# PIC18F2550-USB-HID-LC-Meter.net
KiCad netlist of a schematic drawn in EAGLE
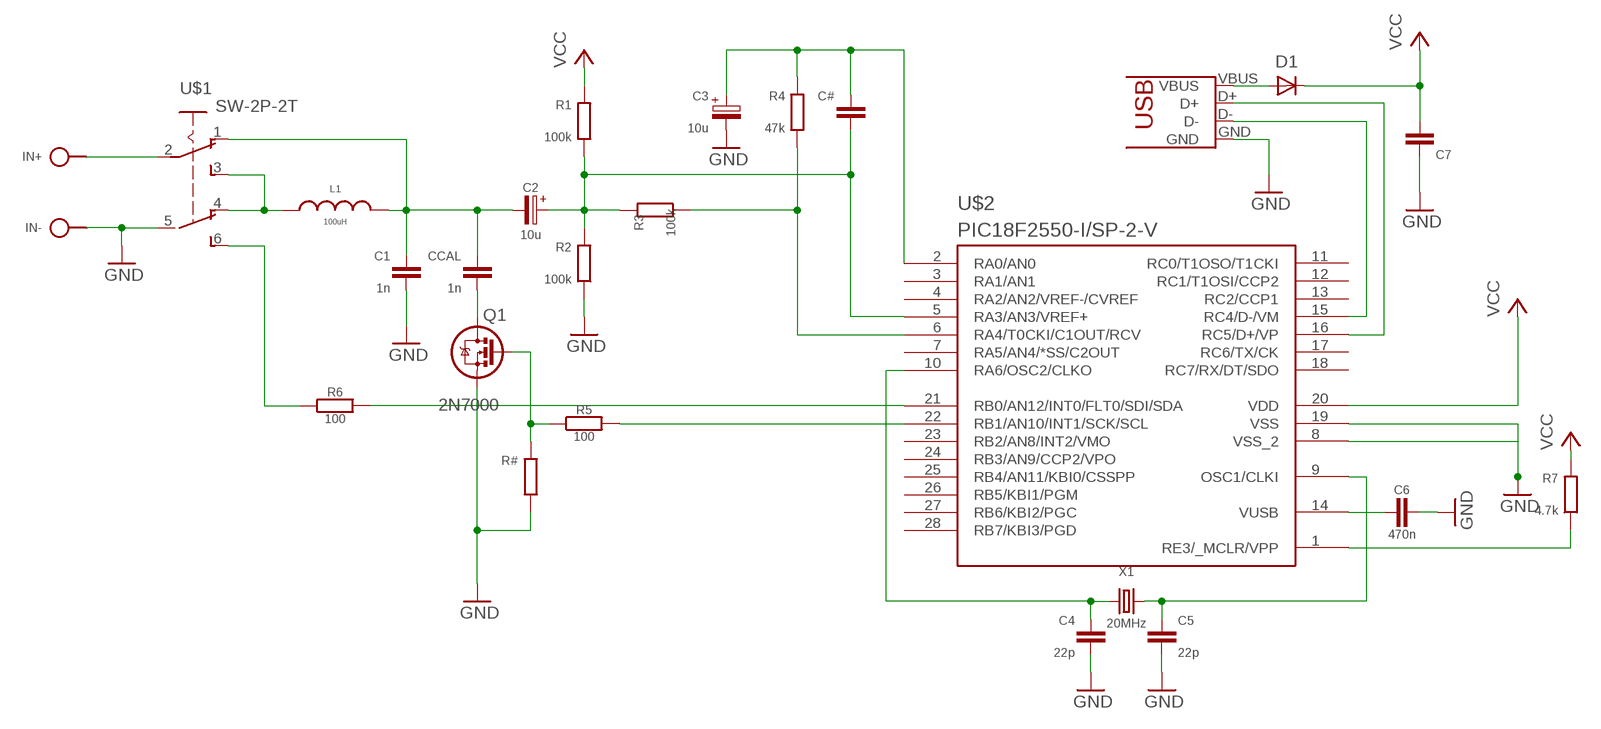
[diagram p0: schematic, sheet 1]

(export (version "E")
  (design (tool "Eeschema 10.0.6"))
  (components
    (comp (ref "C#")
      (value "C050-020X036")
      (footprint "eagle-import:C050-020X036")
      (libsource (lib "eagle-import") (part "C050-020X036"))
    )
    (comp (ref "C1")
      (value "1n")
      (footprint "eagle-import:C050-020X036")
      (libsource (lib "eagle-import") (part "C050-020X036"))
    )
    (comp (ref "C2")
      (value "10u")
      (footprint "eagle-import:E2.5-4_V")
      (libsource (lib "eagle-import") (part "CPOLE2,5-4/V"))
    )
    (comp (ref "C3")
      (value "10u")
      (footprint "eagle-import:E2,5-4")
      (libsource (lib "eagle-import") (part "CPOLE2,5-4"))
    )
    (comp (ref "C4")
      (value "22p")
      (footprint "eagle-import:C025-015X024_V")
      (libsource (lib "eagle-import") (part "C025-015X024"))
    )
    (comp (ref "C5")
      (value "22p")
      (footprint "eagle-import:C025-015X024_V")
      (libsource (lib "eagle-import") (part "C025-015X024"))
    )
    (comp (ref "C6")
      (value "470n")
      (footprint "eagle-import:C050-020X036")
      (libsource (lib "eagle-import") (part "C050-020X036"))
    )
    (comp (ref "C7")
      (value "C050-020X036")
      (footprint "eagle-import:C050-020X036")
      (libsource (lib "eagle-import") (part "C050-020X036"))
    )
    (comp (ref "CCAL")
      (value "1n")
      (footprint "eagle-import:C050-020X036")
      (libsource (lib "eagle-import") (part "C050-020X036"))
    )
    (comp (ref "D1")
      (value "1N414834-5")
      (footprint "eagle-import:DO34-5")
      (libsource (lib "eagle-import") (part "1N414834-5"))
    )
    (comp (ref "IN+")
      (value "SPAD")
      (footprint "eagle-import:SPAD")
      (libsource (lib "eagle-import") (part "SPAD"))
    )
    (comp (ref "IN-")
      (value "SPAD")
      (footprint "eagle-import:SPAD")
      (libsource (lib "eagle-import") (part "SPAD"))
    )
    (comp (ref "J1")
      (value "USB-PRINT")
      (footprint "eagle-import:USB-B-PRINT")
      (libsource (lib "eagle-import") (part "USB-PRINT"))
    )
    (comp (ref "L1")
      (value "100uH")
      (footprint "eagle-import:L-04_7-M")
      (libsource (lib "eagle-import") (part "L04/7-M"))
    )
    (comp (ref "Q1")
      (value "2N7000")
      (footprint "eagle-import:TO92")
      (libsource (lib "eagle-import") (part "2N7000"))
    )
    (comp (ref "R#")
      (value "R0202/7")
      (footprint "eagle-import:0202_7")
      (libsource (lib "eagle-import") (part "R0202/7"))
    )
    (comp (ref "R1")
      (value "100k")
      (footprint "eagle-import:0202_7")
      (libsource (lib "eagle-import") (part "R0202/7"))
    )
    (comp (ref "R2")
      (value "100k")
      (footprint "eagle-import:0202_7")
      (libsource (lib "eagle-import") (part "R0202/7"))
    )
    (comp (ref "R3")
      (value "100k")
      (footprint "eagle-import:0202_7")
      (libsource (lib "eagle-import") (part "R0202/7"))
    )
    (comp (ref "R4")
      (value "47k")
      (footprint "eagle-import:0202_7")
      (libsource (lib "eagle-import") (part "R0202/7"))
    )
    (comp (ref "R5")
      (value "100")
      (footprint "eagle-import:0202_7")
      (libsource (lib "eagle-import") (part "R0202/7"))
    )
    (comp (ref "R6")
      (value "100")
      (footprint "eagle-import:0202_7")
      (libsource (lib "eagle-import") (part "R0202/7"))
    )
    (comp (ref "R7")
      (value "4.7k")
      (footprint "eagle-import:0202_7")
      (libsource (lib "eagle-import") (part "R0202/7"))
    )
    (comp (ref "U$1")
      (value "SW-2P-2T")
      (footprint "eagle-import:SLSW-2P2T")
      (libsource (lib "eagle-import") (part "SW-2P-2T"))
    )
    (comp (ref "U$2")
      (value "PIC18F2550-I/SP-2-V")
      (footprint "eagle-import:DIL28-3_V")
      (libsource (lib "eagle-import") (part "PIC18F2550-I/SP-2-V"))
    )
    (comp (ref "X1")
      (value "20MHz")
      (footprint "eagle-import:HC49")
      (libsource (lib "eagle-import") (part "CRYSTALHC49"))
    )
  )
  (nets
    (net (code "1") (name "GND") (class "Default")
      (node (ref "C1") (pin "2") (pinfunction "2_2") (pintype "passive"))
      (node (ref "C3") (pin "-") (pinfunction "-_-") (pintype "passive"))
      (node (ref "C4") (pin "2") (pinfunction "2_2") (pintype "passive"))
      (node (ref "C5") (pin "2") (pinfunction "2_2") (pintype "passive"))
      (node (ref "C6") (pin "2") (pinfunction "2_2") (pintype "passive"))
      (node (ref "C7") (pin "1") (pinfunction "1_1") (pintype "passive"))
      (node (ref "IN-") (pin "1") (pinfunction "P$1_1") (pintype "bidirectional"))
      (node (ref "J1") (pin "GND") (pinfunction "GND_GND") (pintype "bidirectional"))
      (node (ref "Q1") (pin "1") (pinfunction "S_1") (pintype "passive"))
      (node (ref "R#") (pin "1") (pinfunction "1_1") (pintype "passive"))
      (node (ref "R2") (pin "1") (pinfunction "1_1") (pintype "passive"))
      (node (ref "U$1") (pin "5") (pinfunction "P1_5") (pintype "passive"))
      (node (ref "U$2") (pin "19") (pinfunction "VSS_19") (pintype "passive"))
      (node (ref "U$2") (pin "8") (pinfunction "VSS_2_8") (pintype "passive"))
    )
    (net (code "2") (name "Net-(D1-PadA)") (class "Default")
      (node (ref "D1") (pin "A") (pinfunction "A_A") (pintype "passive"))
      (node (ref "J1") (pin "VBUS") (pinfunction "VBUS_VBUS") (pintype "bidirectional"))
    )
    (net (code "3") (name "Net-(IN+-P$1)") (class "Default")
      (node (ref "IN+") (pin "1") (pinfunction "P$1_1") (pintype "bidirectional"))
      (node (ref "U$1") (pin "2") (pinfunction "P_2") (pintype "passive"))
    )
    (net (code "4") (name "Net-(Q1-D)") (class "Default")
      (node (ref "CCAL") (pin "2") (pinfunction "2_2") (pintype "passive"))
      (node (ref "Q1") (pin "3") (pinfunction "D_3") (pintype "passive"))
    )
    (net (code "5") (name "Net-(Q1-G)") (class "Default")
      (node (ref "Q1") (pin "2") (pinfunction "G_2") (pintype "passive"))
      (node (ref "R#") (pin "2") (pinfunction "2_2") (pintype "passive"))
      (node (ref "R5") (pin "1") (pinfunction "1_1") (pintype "passive"))
    )
    (net (code "6") (name "Net-(U$1-O)") (class "Default")
      (node (ref "C1") (pin "1") (pinfunction "1_1") (pintype "passive"))
      (node (ref "C2") (pin "-") (pinfunction "-_-") (pintype "passive"))
      (node (ref "CCAL") (pin "1") (pinfunction "1_1") (pintype "passive"))
      (node (ref "L1") (pin "2") (pinfunction "2_2") (pintype "passive"))
      (node (ref "U$1") (pin "1") (pinfunction "O_1") (pintype "passive"))
    )
    (net (code "7") (name "Net-(U$1-O1)") (class "Default")
      (node (ref "L1") (pin "1") (pinfunction "1_1") (pintype "passive"))
      (node (ref "U$1") (pin "3") (pinfunction "S_3") (pintype "passive"))
      (node (ref "U$1") (pin "4") (pinfunction "O1_4") (pintype "passive"))
    )
    (net (code "8") (name "Net-(U$1-S1)") (class "Default")
      (node (ref "R6") (pin "1") (pinfunction "1_1") (pintype "passive"))
      (node (ref "U$1") (pin "6") (pinfunction "S1_6") (pintype "passive"))
    )
    (net (code "9") (name "Net-(U$2-OSC1{slash}CLKI)") (class "Default")
      (node (ref "C5") (pin "1") (pinfunction "1_1") (pintype "passive"))
      (node (ref "U$2") (pin "9") (pinfunction "OSC1/CLKI_9") (pintype "passive"))
      (node (ref "X1") (pin "2") (pinfunction "2_2") (pintype "passive"))
    )
    (net (code "10") (name "Net-(U$2-RA0{slash}AN0)") (class "Default")
      (node (ref "C#") (pin "1") (pinfunction "1_1") (pintype "passive"))
      (node (ref "C3") (pin "+") (pinfunction "+_+") (pintype "passive"))
      (node (ref "R4") (pin "2") (pinfunction "2_2") (pintype "passive"))
      (node (ref "U$2") (pin "2") (pinfunction "RA0/AN0_2") (pintype "passive"))
    )
    (net (code "11") (name "Net-(U$2-RA3{slash}AN3{slash}VREF+)") (class "Default")
      (node (ref "C#") (pin "2") (pinfunction "2_2") (pintype "passive"))
      (node (ref "C2") (pin "+") (pinfunction "+_+") (pintype "passive"))
      (node (ref "R1") (pin "1") (pinfunction "1_1") (pintype "passive"))
      (node (ref "R2") (pin "2") (pinfunction "2_2") (pintype "passive"))
      (node (ref "R3") (pin "2") (pinfunction "2_2") (pintype "passive"))
      (node (ref "U$2") (pin "5") (pinfunction "RA3/AN3/VREF+_5") (pintype "passive"))
    )
    (net (code "12") (name "Net-(U$2-RA4{slash}T0CKI{slash}C1OUT{slash}RCV)") (class "Default")
      (node (ref "R3") (pin "1") (pinfunction "1_1") (pintype "passive"))
      (node (ref "R4") (pin "1") (pinfunction "1_1") (pintype "passive"))
      (node (ref "U$2") (pin "6") (pinfunction "RA4/T0CKI/C1OUT/RCV_6") (pintype "passive"))
    )
    (net (code "13") (name "Net-(U$2-RA6{slash}OSC2{slash}CLKO)") (class "Default")
      (node (ref "C4") (pin "1") (pinfunction "1_1") (pintype "passive"))
      (node (ref "U$2") (pin "10") (pinfunction "RA6/OSC2/CLKO_10") (pintype "passive"))
      (node (ref "X1") (pin "1") (pinfunction "1_1") (pintype "passive"))
    )
    (net (code "14") (name "Net-(U$2-RB0{slash}AN12{slash}INT0{slash}FLT0{slash}SDI{slash}SDA)") (class "Default")
      (node (ref "R6") (pin "2") (pinfunction "2_2") (pintype "passive"))
      (node (ref "U$2") (pin "21") (pinfunction "RB0/AN12/INT0/FLT0/SDI/SDA_21") (pintype "passive"))
    )
    (net (code "15") (name "Net-(U$2-RB1{slash}AN10{slash}INT1{slash}SCK{slash}SCL)") (class "Default")
      (node (ref "R5") (pin "2") (pinfunction "2_2") (pintype "passive"))
      (node (ref "U$2") (pin "22") (pinfunction "RB1/AN10/INT1/SCK/SCL_22") (pintype "passive"))
    )
    (net (code "16") (name "Net-(U$2-RC4{slash}D-{slash}VM)") (class "Default")
      (node (ref "J1") (pin "D-") (pinfunction "D-_D-") (pintype "bidirectional"))
      (node (ref "U$2") (pin "15") (pinfunction "RC4/D-/VM_15") (pintype "passive"))
    )
    (net (code "17") (name "Net-(U$2-RC5{slash}D+{slash}VP)") (class "Default")
      (node (ref "J1") (pin "D+") (pinfunction "D+_D+") (pintype "bidirectional"))
      (node (ref "U$2") (pin "16") (pinfunction "RC5/D+/VP_16") (pintype "passive"))
    )
    (net (code "18") (name "Net-(U$2-RE3{slash}_MCLR{slash}VPP)") (class "Default")
      (node (ref "R7") (pin "1") (pinfunction "1_1") (pintype "passive"))
      (node (ref "U$2") (pin "1") (pinfunction "RE3/_MCLR/VPP_1") (pintype "passive"))
    )
    (net (code "19") (name "Net-(U$2-VUSB)") (class "Default")
      (node (ref "C6") (pin "1") (pinfunction "1_1") (pintype "passive"))
      (node (ref "U$2") (pin "14") (pinfunction "VUSB_14") (pintype "passive"))
    )
    (net (code "20") (name "VCC") (class "Default")
      (node (ref "C7") (pin "2") (pinfunction "2_2") (pintype "passive"))
      (node (ref "D1") (pin "C") (pinfunction "C_C") (pintype "passive"))
      (node (ref "R1") (pin "2") (pinfunction "2_2") (pintype "passive"))
      (node (ref "R7") (pin "2") (pinfunction "2_2") (pintype "passive"))
      (node (ref "U$2") (pin "20") (pinfunction "VDD_20") (pintype "passive"))
    )
    (net (code "21") (name "unconnected-(U$2-RA1{slash}AN1-Pad3)") (class "Default")
      (node (ref "U$2") (pin "3") (pinfunction "RA1/AN1_3") (pintype "passive"))
    )
    (net (code "22") (name "unconnected-(U$2-RA2{slash}AN2{slash}VREF-{slash}CVREF-Pad4)") (class "Default")
      (node (ref "U$2") (pin "4") (pinfunction "RA2/AN2/VREF-/CVREF_4") (pintype "passive"))
    )
    (net (code "23") (name "unconnected-(U$2-RA5{slash}AN4{slash}*SS{slash}C2OUT-Pad7)") (class "Default")
      (node (ref "U$2") (pin "7") (pinfunction "RA5/AN4/*SS/C2OUT_7") (pintype "passive"))
    )
    (net (code "24") (name "unconnected-(U$2-RB2{slash}AN8{slash}INT2{slash}VMO-Pad23)") (class "Default")
      (node (ref "U$2") (pin "23") (pinfunction "RB2/AN8/INT2/VMO_23") (pintype "passive"))
    )
    (net (code "25") (name "unconnected-(U$2-RB3{slash}AN9{slash}CCP2{slash}VPO-Pad24)") (class "Default")
      (node (ref "U$2") (pin "24") (pinfunction "RB3/AN9/CCP2/VPO_24") (pintype "passive"))
    )
    (net (code "26") (name "unconnected-(U$2-RB4{slash}AN11{slash}KBI0{slash}CSSPP-Pad25)") (class "Default")
      (node (ref "U$2") (pin "25") (pinfunction "RB4/AN11/KBI0/CSSPP_25") (pintype "passive"))
    )
    (net (code "27") (name "unconnected-(U$2-RB5{slash}KBI1{slash}PGM-Pad26)") (class "Default")
      (node (ref "U$2") (pin "26") (pinfunction "RB5/KBI1/PGM_26") (pintype "passive"))
    )
    (net (code "28") (name "unconnected-(U$2-RB6{slash}KBI2{slash}PGC-Pad27)") (class "Default")
      (node (ref "U$2") (pin "27") (pinfunction "RB6/KBI2/PGC_27") (pintype "passive"))
    )
    (net (code "29") (name "unconnected-(U$2-RB7{slash}KBI3{slash}PGD-Pad28)") (class "Default")
      (node (ref "U$2") (pin "28") (pinfunction "RB7/KBI3/PGD_28") (pintype "passive"))
    )
    (net (code "30") (name "unconnected-(U$2-RC0{slash}T1OSO{slash}T1CKI-Pad11)") (class "Default")
      (node (ref "U$2") (pin "11") (pinfunction "RC0/T1OSO/T1CKI_11") (pintype "passive"))
    )
    (net (code "31") (name "unconnected-(U$2-RC1{slash}T1OSI{slash}CCP2-Pad12)") (class "Default")
      (node (ref "U$2") (pin "12") (pinfunction "RC1/T1OSI/CCP2_12") (pintype "passive"))
    )
    (net (code "32") (name "unconnected-(U$2-RC2{slash}CCP1-Pad13)") (class "Default")
      (node (ref "U$2") (pin "13") (pinfunction "RC2/CCP1_13") (pintype "passive"))
    )
    (net (code "33") (name "unconnected-(U$2-RC6{slash}TX{slash}CK-Pad17)") (class "Default")
      (node (ref "U$2") (pin "17") (pinfunction "RC6/TX/CK_17") (pintype "passive"))
    )
    (net (code "34") (name "unconnected-(U$2-RC7{slash}RX{slash}DT{slash}SDO-Pad18)") (class "Default")
      (node (ref "U$2") (pin "18") (pinfunction "RC7/RX/DT/SDO_18") (pintype "passive"))
    )
  )
)
